# soil_temp_v0_1.net
KiCad netlist of a schematic drawn in EAGLE
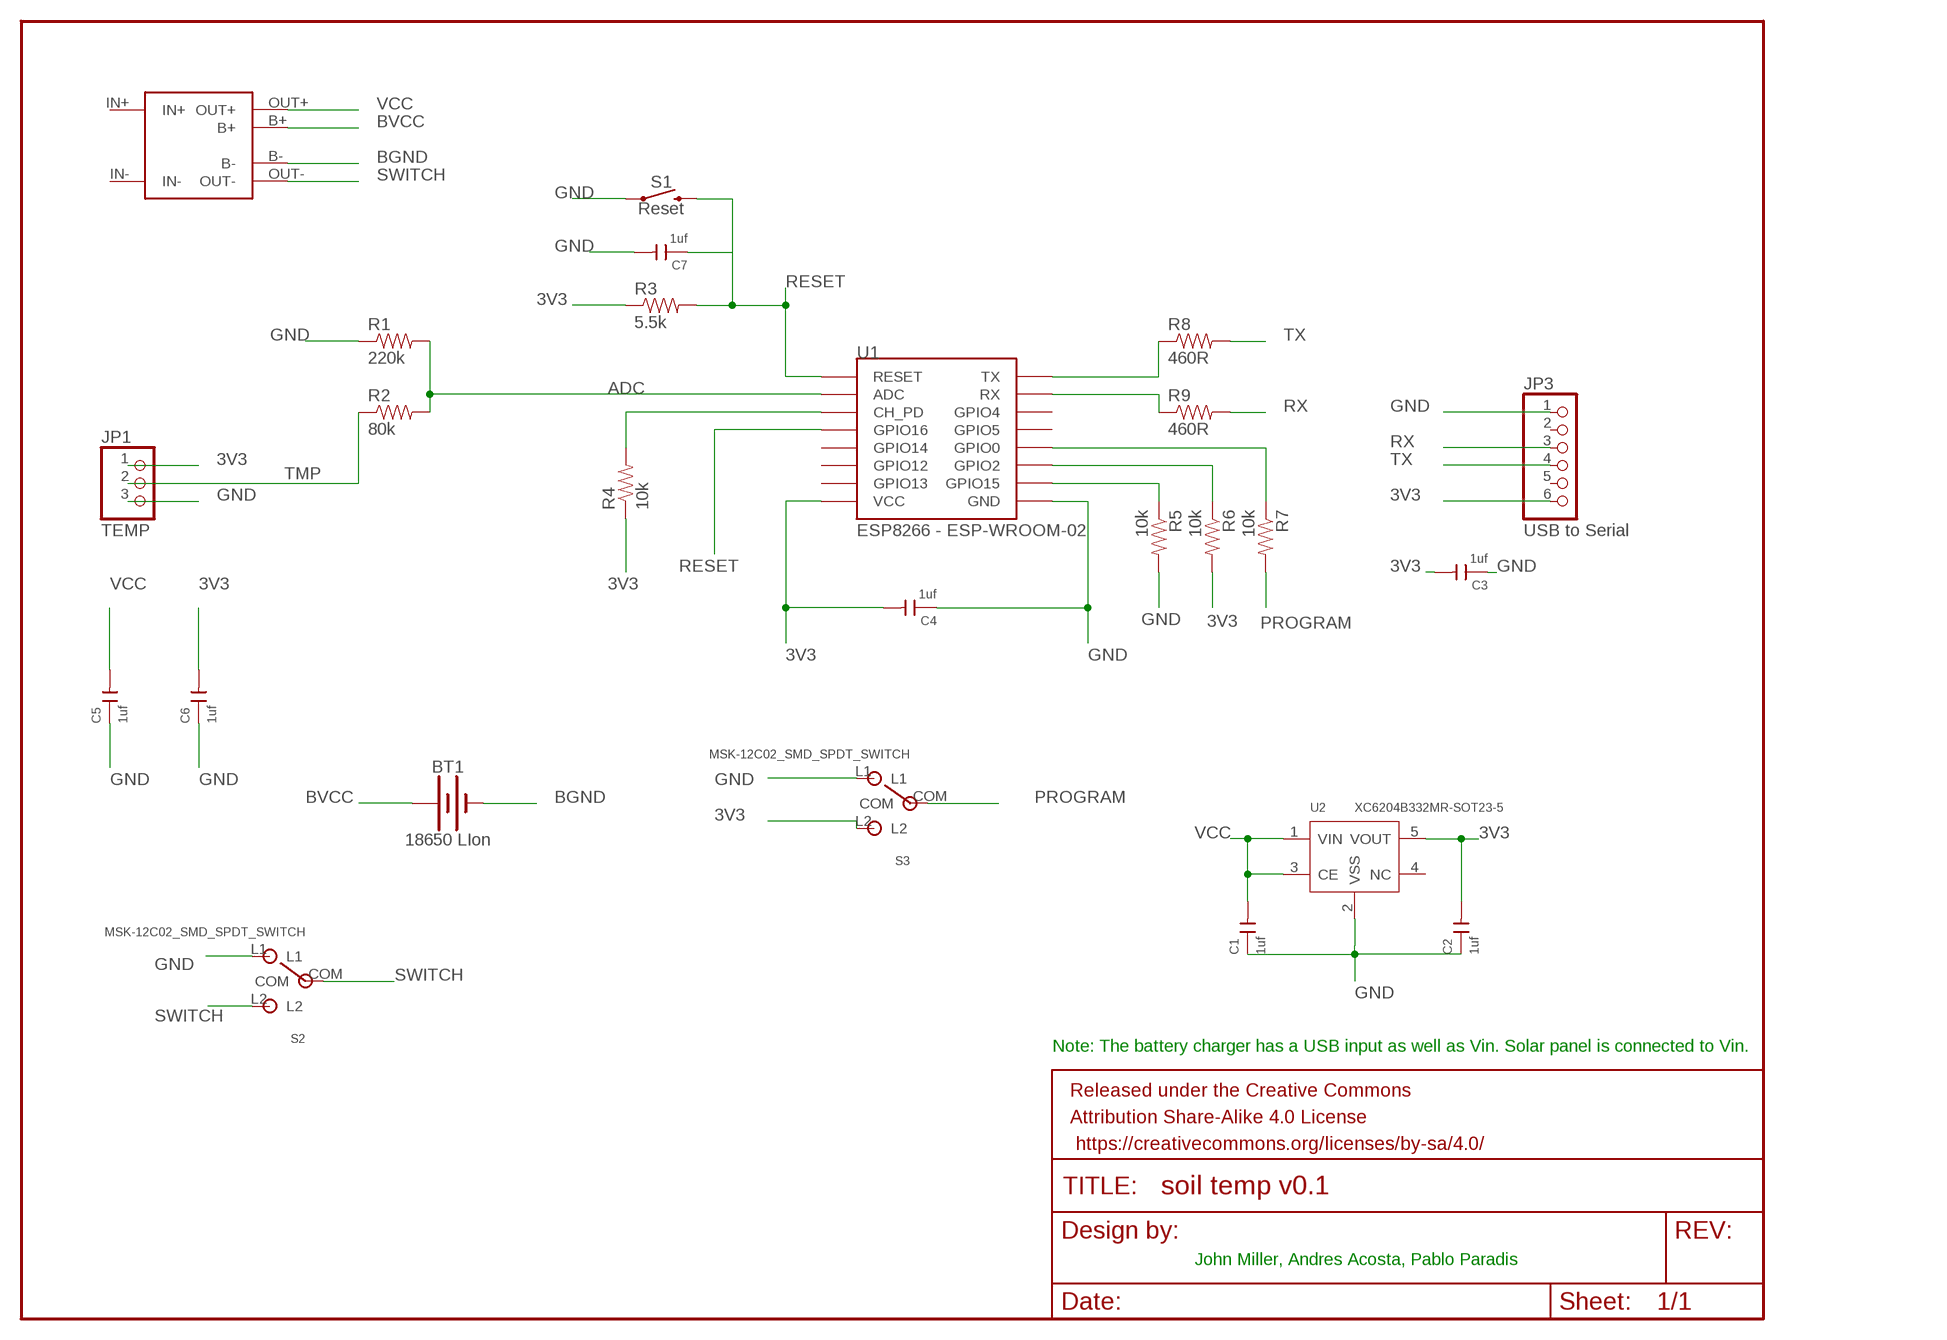
[diagram p0: schematic, sheet 1]

(export (version "E")
  (design (tool "Eeschema 10.0.6"))
  (components
    (comp (ref "BT1")
      (value "18650 LIon")
      (footprint "eagle-import:BATTERY_18650-HOLDER")
      (libsource (lib "eagle-import") (part "BATTERY-18650"))
    )
    (comp (ref "C1")
      (value "1uf")
      (footprint "eagle-import:C0805")
      (fields (field (name "MPN") "CC0805KKX7R8BB105"))
      (libsource (lib "eagle-import") (part "CERAMIC-1UF-25V-10%-X7R(0805)"))
    )
    (comp (ref "C2")
      (value "1uf")
      (footprint "eagle-import:C0805")
      (fields (field (name "MPN") "CC0805KKX7R8BB105"))
      (libsource (lib "eagle-import") (part "CERAMIC-1UF-25V-10%-X7R(0805)"))
    )
    (comp (ref "C3")
      (value "1uf")
      (footprint "eagle-import:C0805")
      (fields (field (name "MPN") "CC0805KKX7R8BB105"))
      (libsource (lib "eagle-import") (part "CERAMIC-1UF-25V-10%-X7R(0805)"))
    )
    (comp (ref "C4")
      (value "1uf")
      (footprint "eagle-import:C0805")
      (fields (field (name "MPN") "CC0805KKX7R8BB105"))
      (libsource (lib "eagle-import") (part "CERAMIC-1UF-25V-10%-X7R(0805)"))
    )
    (comp (ref "C5")
      (value "1uf")
      (footprint "eagle-import:C0805")
      (fields (field (name "MPN") "CC0805KKX7R8BB105"))
      (libsource (lib "eagle-import") (part "CERAMIC-1UF-25V-10%-X7R(0805)"))
    )
    (comp (ref "C6")
      (value "1uf")
      (footprint "eagle-import:C0805")
      (fields (field (name "MPN") "CC0805KKX7R8BB105"))
      (libsource (lib "eagle-import") (part "CERAMIC-1UF-25V-10%-X7R(0805)"))
    )
    (comp (ref "C7")
      (value "1uf")
      (footprint "eagle-import:C0805")
      (fields (field (name "MPN") "CC0805KKX7R8BB105"))
      (libsource (lib "eagle-import") (part "CERAMIC-1UF-25V-10%-X7R(0805)"))
    )
    (comp (ref "FRAME1")
      (value "FRAME-LETTERNO_PACKAGE")
      (footprint "eagle-import:DUMMY")
      (fields (field (name "DESIGNER") "Nobody"))
      (libsource (lib "eagle-import") (part "FRAME-LETTERNO_PACKAGE"))
    )
    (comp (ref "JP1")
      (value "TEMP")
      (footprint "eagle-import:1X03")
      (libsource (lib "eagle-import") (part "PINHD-1X3"))
    )
    (comp (ref "JP3")
      (value "USB to Serial")
      (footprint "eagle-import:1X06_90")
      (libsource (lib "eagle-import") (part "PINHD-1X6/90"))
    )
    (comp (ref "R1")
      (value "220k")
      (footprint "eagle-import:R0805")
      (libsource (lib "eagle-import") (part "RESISTOR0805"))
    )
    (comp (ref "R2")
      (value "80k")
      (footprint "eagle-import:R0805")
      (libsource (lib "eagle-import") (part "RESISTOR0805"))
    )
    (comp (ref "R3")
      (value "5.5k")
      (footprint "eagle-import:R0805")
      (libsource (lib "eagle-import") (part "RESISTOR0805"))
    )
    (comp (ref "R4")
      (value "10k")
      (footprint "eagle-import:R0805")
      (libsource (lib "eagle-import") (part "RESISTOR0805"))
    )
    (comp (ref "R5")
      (value "10k")
      (footprint "eagle-import:R0805")
      (libsource (lib "eagle-import") (part "RESISTOR0805"))
    )
    (comp (ref "R6")
      (value "10k")
      (footprint "eagle-import:R0805")
      (libsource (lib "eagle-import") (part "RESISTOR0805"))
    )
    (comp (ref "R7")
      (value "10k")
      (footprint "eagle-import:R0805")
      (libsource (lib "eagle-import") (part "RESISTOR0805"))
    )
    (comp (ref "R8")
      (value "460R")
      (footprint "eagle-import:R0805")
      (libsource (lib "eagle-import") (part "RESISTOR0805"))
    )
    (comp (ref "R9")
      (value "460R")
      (footprint "eagle-import:R0805")
      (libsource (lib "eagle-import") (part "RESISTOR0805"))
    )
    (comp (ref "S1")
      (value "Reset")
      (footprint "eagle-import:TACTILE_SWITCH_SMD_6.2MM_TALL")
      (libsource (lib "eagle-import") (part "MOMENTARY-SWITCH-SPST-SMD-6.2MM-TALL"))
    )
    (comp (ref "S2")
      (value "MSK-12C02_SMD_SPDT_SWITCH")
      (footprint "eagle-import:MSK-12C02")
      (libsource (lib "eagle-import") (part "MSK-12C02_SMD_SPDT_SWITCH"))
    )
    (comp (ref "S3")
      (value "MSK-12C02_SMD_SPDT_SWITCH")
      (footprint "eagle-import:MSK-12C02")
      (libsource (lib "eagle-import") (part "MSK-12C02_SMD_SPDT_SWITCH"))
    )
    (comp (ref "U1")
      (value "ESP8266 - ESP-WROOM-02")
      (footprint "eagle-import:ESP12")
      (libsource (lib "eagle-import") (part "ESP12"))
    )
    (comp (ref "U2")
      (value "XC6204B332MR-SOT23-5")
      (footprint "eagle-import:SOT-23-5")
      (fields (field (name "MPN") "XC6204B332MR"))
      (libsource (lib "eagle-import") (part "PMIC-LDO-XC6204B332MR(SOT23-5)"))
    )
    (comp (ref "U3")
      (value "TP4056-MODULE")
      (footprint "eagle-import:TP4056-LITHIUM-PROTECTED-MODULE")
      (libsource (lib "eagle-import") (part "TP4056-MODULE"))
    )
  )
  (nets
    (net (code "1") (name "/3V3") (class "Default")
      (node (ref "C2") (pin "2") (pinfunction "2_2") (pintype "passive"))
      (node (ref "C3") (pin "2") (pinfunction "2_2") (pintype "passive"))
      (node (ref "C4") (pin "2") (pinfunction "2_2") (pintype "passive"))
      (node (ref "C6") (pin "2") (pinfunction "2_2") (pintype "passive"))
      (node (ref "JP1") (pin "1") (pinfunction "1_1") (pintype "passive"))
      (node (ref "JP3") (pin "6") (pinfunction "6_6") (pintype "passive"))
      (node (ref "R3") (pin "1") (pinfunction "1_1") (pintype "passive"))
      (node (ref "R4") (pin "1") (pinfunction "1_1") (pintype "passive"))
      (node (ref "R6") (pin "2") (pinfunction "2_2") (pintype "passive"))
      (node (ref "S3") (pin "L2") (pinfunction "L2_L2") (pintype "bidirectional"))
      (node (ref "U1") (pin "VCC") (pinfunction "VCC_VCC") (pintype "bidirectional"))
      (node (ref "U2") (pin "5") (pinfunction "VOUT_5") (pintype "output"))
    )
    (net (code "2") (name "/ADC") (class "Default")
      (node (ref "R1") (pin "2") (pinfunction "2_2") (pintype "passive"))
      (node (ref "R2") (pin "2") (pinfunction "2_2") (pintype "passive"))
      (node (ref "U1") (pin "ADC") (pinfunction "ADC_ADC") (pintype "bidirectional"))
    )
    (net (code "3") (name "/BGND") (class "Default")
      (node (ref "BT1") (pin "GND@1") (pinfunction "-_GND@1") (pintype "power_in"))
      (node (ref "U3") (pin "B-") (pinfunction "B-_B-") (pintype "power_in"))
    )
    (net (code "4") (name "/BVCC") (class "Default")
      (node (ref "BT1") (pin "PWR@1") (pinfunction "+_PWR@1") (pintype "power_in"))
      (node (ref "U3") (pin "B+") (pinfunction "B+_B+") (pintype "power_in"))
    )
    (net (code "5") (name "/GND") (class "Default")
      (node (ref "C1") (pin "1") (pinfunction "1_1") (pintype "passive"))
      (node (ref "C2") (pin "1") (pinfunction "1_1") (pintype "passive"))
      (node (ref "C3") (pin "1") (pinfunction "1_1") (pintype "passive"))
      (node (ref "C4") (pin "1") (pinfunction "1_1") (pintype "passive"))
      (node (ref "C5") (pin "1") (pinfunction "1_1") (pintype "passive"))
      (node (ref "C6") (pin "1") (pinfunction "1_1") (pintype "passive"))
      (node (ref "C7") (pin "2") (pinfunction "2_2") (pintype "passive"))
      (node (ref "JP1") (pin "3") (pinfunction "3_3") (pintype "passive"))
      (node (ref "JP3") (pin "1") (pinfunction "1_1") (pintype "passive"))
      (node (ref "R1") (pin "1") (pinfunction "1_1") (pintype "passive"))
      (node (ref "R5") (pin "2") (pinfunction "2_2") (pintype "passive"))
      (node (ref "S1") (pin "A2") (pinfunction "1_A2") (pintype "passive"))
      (node (ref "S2") (pin "L1") (pinfunction "L1_L1") (pintype "bidirectional"))
      (node (ref "S3") (pin "L1") (pinfunction "L1_L1") (pintype "bidirectional"))
      (node (ref "U1") (pin "GND") (pinfunction "GND_GND") (pintype "bidirectional"))
      (node (ref "U2") (pin "2") (pinfunction "VSS_2") (pintype "power_in"))
    )
    (net (code "6") (name "/IN+") (class "Default")
      (node (ref "U3") (pin "IN+") (pinfunction "IN+_IN+") (pintype "power_in"))
    )
    (net (code "7") (name "/IN-") (class "Default")
      (node (ref "U3") (pin "IN-") (pinfunction "IN-_IN-") (pintype "power_in"))
    )
    (net (code "8") (name "/PROGRAM") (class "Default")
      (node (ref "R7") (pin "2") (pinfunction "2_2") (pintype "passive"))
      (node (ref "S3") (pin "COM") (pinfunction "COM_COM") (pintype "bidirectional"))
    )
    (net (code "9") (name "/RESET") (class "Default")
      (node (ref "C7") (pin "1") (pinfunction "1_1") (pintype "passive"))
      (node (ref "R3") (pin "2") (pinfunction "2_2") (pintype "passive"))
      (node (ref "S1") (pin "B2") (pinfunction "2_B2") (pintype "passive"))
      (node (ref "U1") (pin "GPIO16") (pinfunction "GPIO16_GPIO16") (pintype "bidirectional"))
      (node (ref "U1") (pin "RESET") (pinfunction "RESET_RESET") (pintype "bidirectional"))
    )
    (net (code "10") (name "/RX") (class "Default")
      (node (ref "JP3") (pin "3") (pinfunction "3_3") (pintype "passive"))
      (node (ref "R9") (pin "2") (pinfunction "2_2") (pintype "passive"))
    )
    (net (code "11") (name "/SWITCH") (class "Default")
      (node (ref "S2") (pin "COM") (pinfunction "COM_COM") (pintype "bidirectional"))
      (node (ref "S2") (pin "L2") (pinfunction "L2_L2") (pintype "bidirectional"))
      (node (ref "U3") (pin "OUT-") (pinfunction "OUT-_OUT-") (pintype "power_in"))
    )
    (net (code "12") (name "/TMP") (class "Default")
      (node (ref "JP1") (pin "2") (pinfunction "2_2") (pintype "passive"))
      (node (ref "R2") (pin "1") (pinfunction "1_1") (pintype "passive"))
    )
    (net (code "13") (name "/TX") (class "Default")
      (node (ref "JP3") (pin "4") (pinfunction "4_4") (pintype "passive"))
      (node (ref "R8") (pin "2") (pinfunction "2_2") (pintype "passive"))
    )
    (net (code "14") (name "/VCC") (class "Default")
      (node (ref "C1") (pin "2") (pinfunction "2_2") (pintype "passive"))
      (node (ref "C5") (pin "2") (pinfunction "2_2") (pintype "passive"))
      (node (ref "U2") (pin "1") (pinfunction "VIN_1") (pintype "input"))
      (node (ref "U2") (pin "3") (pinfunction "CE_3") (pintype "bidirectional"))
      (node (ref "U3") (pin "OUT+") (pinfunction "OUT+_OUT+") (pintype "power_in"))
    )
    (net (code "15") (name "Net-(R4-Pad2)") (class "Default")
      (node (ref "R4") (pin "2") (pinfunction "2_2") (pintype "passive"))
      (node (ref "U1") (pin "CH_PD") (pinfunction "CH_PD_CH_PD") (pintype "bidirectional"))
    )
    (net (code "16") (name "Net-(R5-Pad1)") (class "Default")
      (node (ref "R5") (pin "1") (pinfunction "1_1") (pintype "passive"))
      (node (ref "U1") (pin "GPIO15") (pinfunction "GPIO15_GPIO15") (pintype "bidirectional"))
    )
    (net (code "17") (name "Net-(R6-Pad1)") (class "Default")
      (node (ref "R6") (pin "1") (pinfunction "1_1") (pintype "passive"))
      (node (ref "U1") (pin "GPIO2") (pinfunction "GPIO2_GPIO2") (pintype "bidirectional"))
    )
    (net (code "18") (name "Net-(R7-Pad1)") (class "Default")
      (node (ref "R7") (pin "1") (pinfunction "1_1") (pintype "passive"))
      (node (ref "U1") (pin "GPIO0") (pinfunction "GPIO0_GPIO0") (pintype "bidirectional"))
    )
    (net (code "19") (name "Net-(R8-Pad1)") (class "Default")
      (node (ref "R8") (pin "1") (pinfunction "1_1") (pintype "passive"))
      (node (ref "U1") (pin "TX") (pinfunction "TX_TX") (pintype "bidirectional"))
    )
    (net (code "20") (name "Net-(R9-Pad1)") (class "Default")
      (node (ref "R9") (pin "1") (pinfunction "1_1") (pintype "passive"))
      (node (ref "U1") (pin "RX") (pinfunction "RX_RX") (pintype "bidirectional"))
    )
    (net (code "21") (name "unconnected-(JP3-Pad2)") (class "Default")
      (node (ref "JP3") (pin "2") (pinfunction "2_2") (pintype "passive"))
    )
    (net (code "22") (name "unconnected-(JP3-Pad5)") (class "Default")
      (node (ref "JP3") (pin "5") (pinfunction "5_5") (pintype "passive"))
    )
    (net (code "23") (name "unconnected-(U1-PadGPIO4)") (class "Default")
      (node (ref "U1") (pin "GPIO4") (pinfunction "GPIO4_GPIO4") (pintype "bidirectional"))
    )
    (net (code "24") (name "unconnected-(U1-PadGPIO5)") (class "Default")
      (node (ref "U1") (pin "GPIO5") (pinfunction "GPIO5_GPIO5") (pintype "bidirectional"))
    )
    (net (code "25") (name "unconnected-(U1-PadGPIO12)") (class "Default")
      (node (ref "U1") (pin "GPIO12") (pinfunction "GPIO12_GPIO12") (pintype "bidirectional"))
    )
    (net (code "26") (name "unconnected-(U1-PadGPIO13)") (class "Default")
      (node (ref "U1") (pin "GPIO13") (pinfunction "GPIO13_GPIO13") (pintype "bidirectional"))
    )
    (net (code "27") (name "unconnected-(U1-PadGPIO14)") (class "Default")
      (node (ref "U1") (pin "GPIO14") (pinfunction "GPIO14_GPIO14") (pintype "bidirectional"))
    )
    (net (code "28") (name "unconnected-(U2-NC-Pad4)") (class "Default")
      (node (ref "U2") (pin "4") (pinfunction "NC_4") (pintype "no_connect"))
    )
  )
)
